# Sheet1.net
KiCad netlist of a schematic drawn in Altium Designer
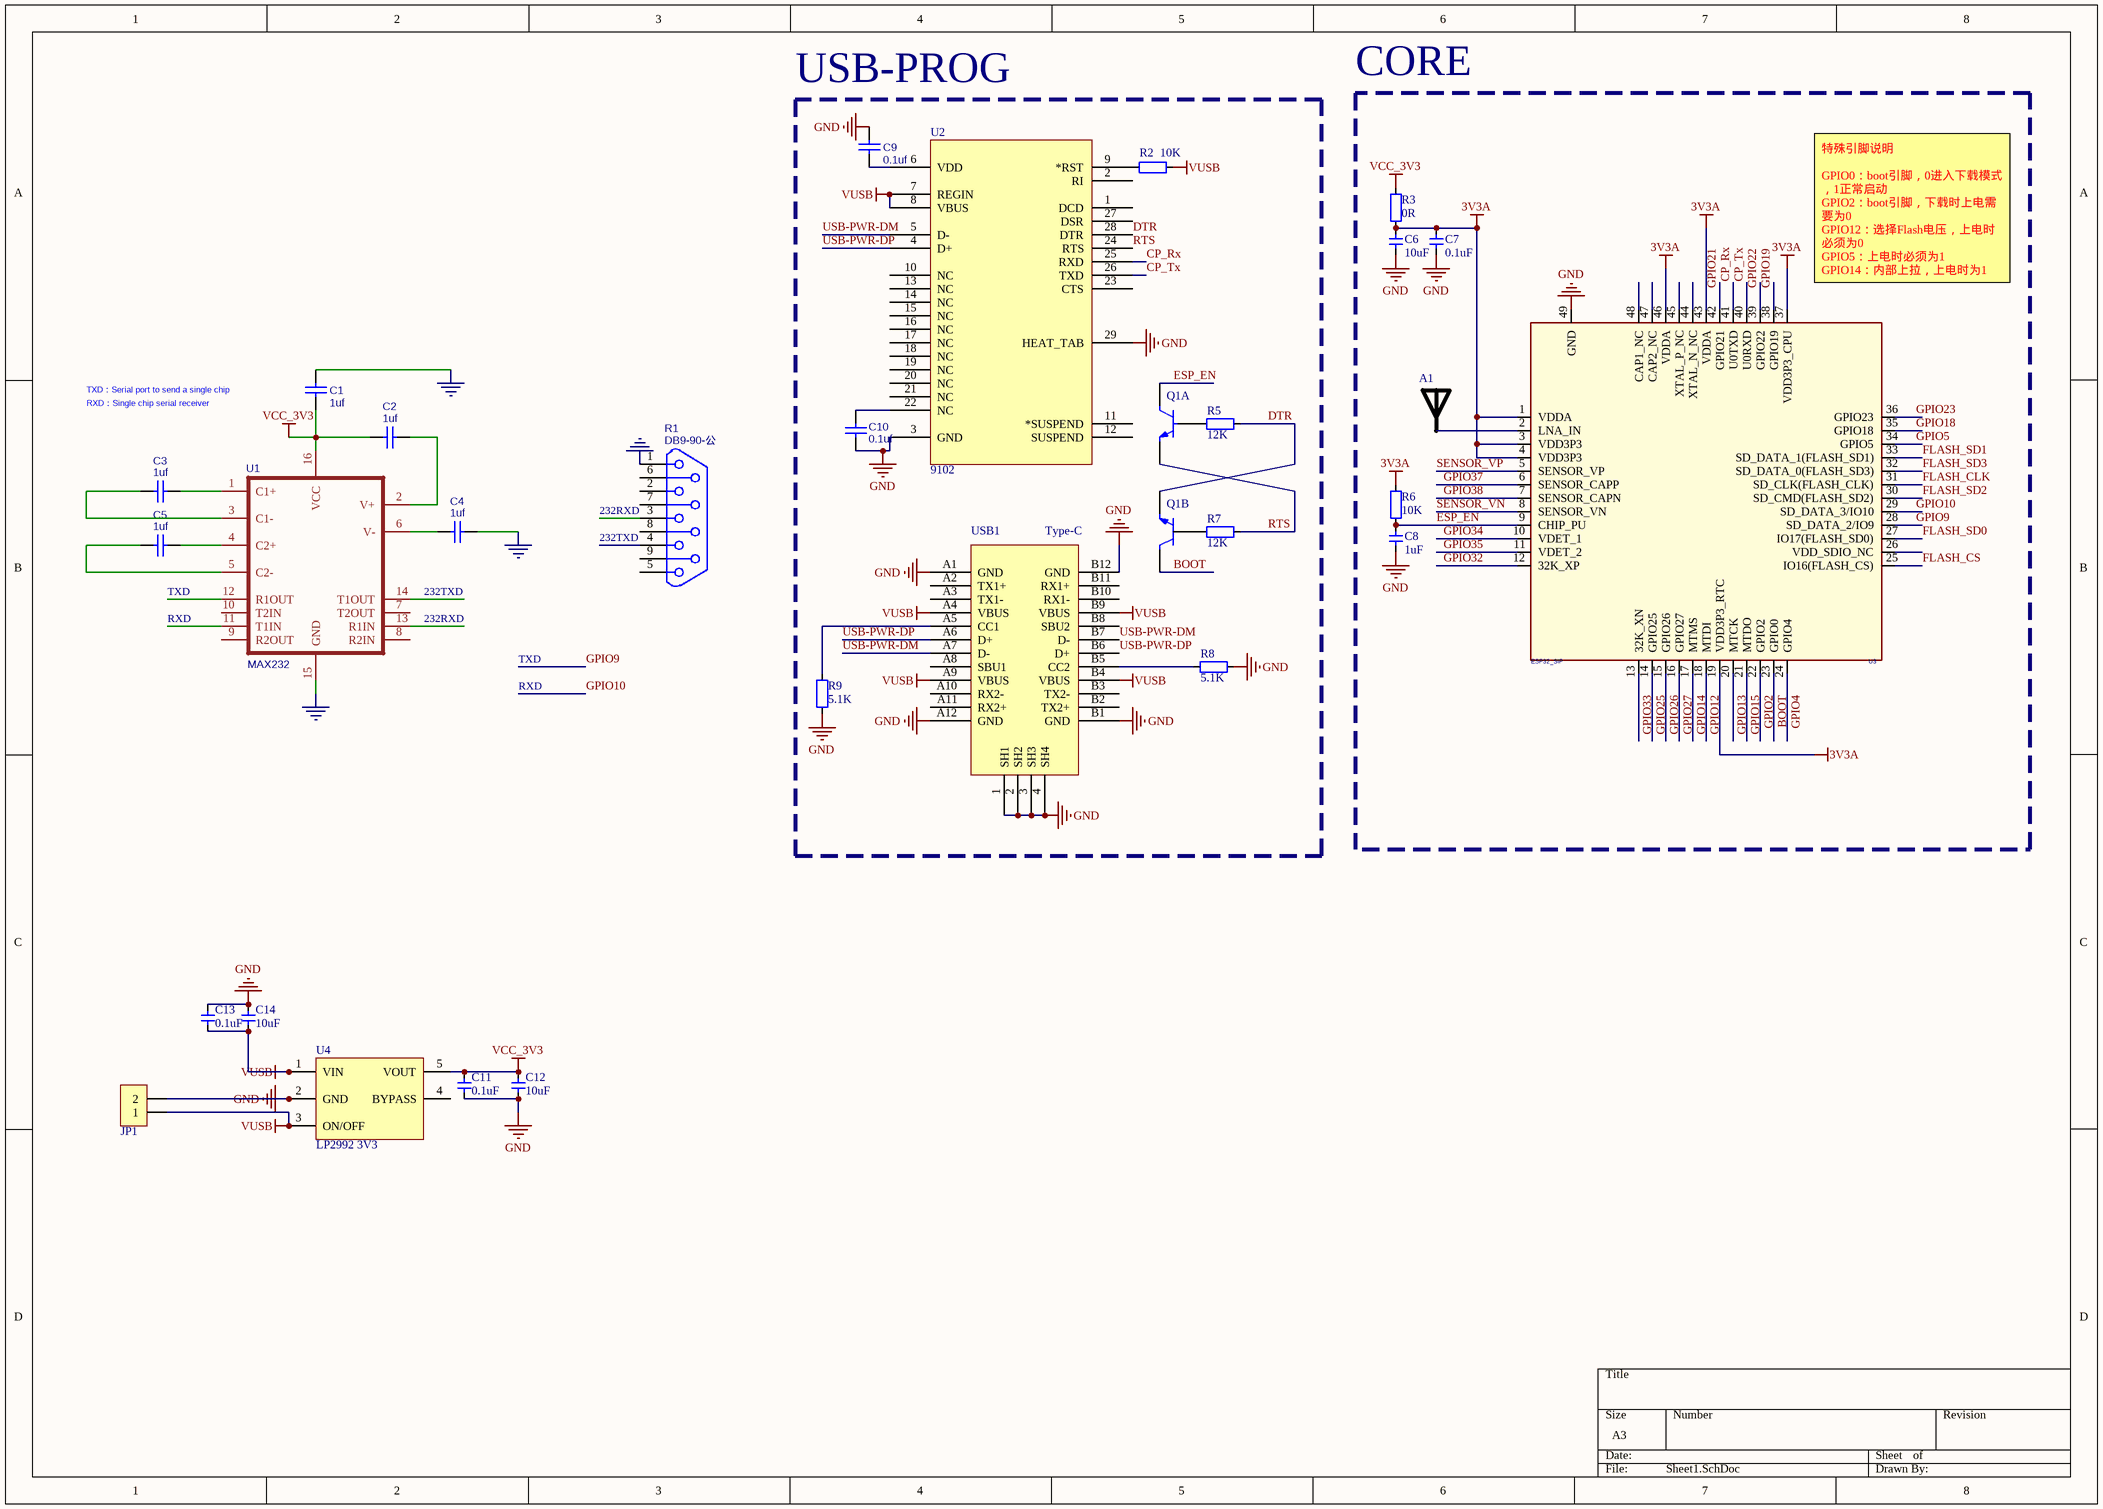
[diagram p0: Sheet1.SchDoc]

(export (version "E")
  (design (tool "Eeschema 10.0.6"))
  (components
    (comp (ref "A1")
      (value "RAINSUN")
      (footprint "ANT-Rainsun-AN5120")
      (libsource (lib "MyPcbLib") (part "ANT-Rainsun-AP5120"))
    )
    (comp (ref "C1")
      (value "1uf")
      (footprint "C0402_M")
      (fields (field (name "BOM_MANUFACTURER PART") "?"))
      (libsource (lib "altium-import") (part "root_2_1uf_"))
    )
    (comp (ref "C2")
      (value "1uf")
      (footprint "C0402_M")
      (fields (field (name "BOM_MANUFACTURER PART") "?"))
      (libsource (lib "altium-import") (part "root_1_1uf_"))
    )
    (comp (ref "C3")
      (value "1uf")
      (footprint "C0402_M")
      (fields (field (name "BOM_MANUFACTURER PART") "?"))
      (libsource (lib "altium-import") (part "root_1_1uf_"))
    )
    (comp (ref "C4")
      (value "1uf")
      (footprint "C0402_M")
      (fields (field (name "BOM_MANUFACTURER PART") "?"))
      (libsource (lib "altium-import") (part "root_1_1uf_"))
    )
    (comp (ref "C5")
      (value "1uf")
      (footprint "C0402_M")
      (fields (field (name "BOM_MANUFACTURER PART") "?"))
      (libsource (lib "altium-import") (part "root_1_1uf_"))
    )
    (comp (ref "C6")
      (value "10uF")
      (footprint "CAP_0402")
      (description "Capacitor")
      (libsource (lib "MyPcbLib") (part "电容-0402"))
    )
    (comp (ref "C7")
      (value "0.1uF")
      (footprint "CAP_0402")
      (description "Capacitor")
      (libsource (lib "MyPcbLib") (part "电容-0402"))
    )
    (comp (ref "C8")
      (value "1uF")
      (footprint "CAP_0402")
      (description "Capacitor")
      (libsource (lib "MyPcbLib") (part "电容-0402"))
    )
    (comp (ref "C9")
      (value "0.1uf")
      (footprint "C0402_M")
      (fields (field (name "BOM_MANUFACTURER PART") "?"))
      (libsource (lib "altium-import") (part "root_2_1uf_"))
    )
    (comp (ref "C10")
      (value "0.1uf")
      (footprint "C0402_M")
      (fields (field (name "BOM_MANUFACTURER PART") "?"))
      (libsource (lib "altium-import") (part "root_0_1uf_"))
    )
    (comp (ref "C11")
      (value "0.1uF")
      (footprint "CAP_0402")
      (description "Capacitor")
      (libsource (lib "MyPcbLib") (part "电容-0402"))
    )
    (comp (ref "C12")
      (value "10uF")
      (footprint "CAP_0402")
      (description "Capacitor")
      (libsource (lib "MyPcbLib") (part "电容-0402"))
    )
    (comp (ref "C13")
      (value "0.1uF")
      (footprint "CAP_0402")
      (description "Capacitor")
      (libsource (lib "MyPcbLib") (part "电容-0402"))
    )
    (comp (ref "C14")
      (value "10uF")
      (footprint "CAP_0402")
      (description "Capacitor")
      (libsource (lib "MyPcbLib") (part "电容-0402"))
    )
    (comp (ref "JP1")
      (value "HDR-1X2")
      (footprint "XH2.54-LI-2P")
      (description "2P接插件")
      (libsource (lib "5.5 - 2.54mm连接器(KF2EDGK_XH2.54_2.54排针排母)") (part "Header 2"))
    )
    (comp (ref "Q1")
      (value "BC847BVC-7")
      (footprint "SOT563-6")
      (libsource (lib "MyPcbLib") (part "BC847BVC-7"))
    )
    (comp (ref "R1")
      (value "DB9-90-公")
      (footprint "DSUB-TH_FDB0901-M0DB300K6KF")
      (fields (field (name "BOM_MANUFACTURER PART") "?"))
      (libsource (lib "altium-import") (part "root_0_DB9-90-公_"))
    )
    (comp (ref "R2")
      (value "10K")
      (footprint "RES_0402")
      (description "Resistor")
      (libsource (lib "") (part "电阻-0402_1"))
    )
    (comp (ref "R3")
      (value "0R")
      (footprint "RES_0402")
      (description "Resistor")
      (libsource (lib "MyPcbLib") (part "电阻-0402"))
    )
    (comp (ref "R5")
      (value "12K")
      (footprint "RES_0402")
      (description "Resistor")
      (libsource (lib "") (part "电阻-0402_1"))
    )
    (comp (ref "R6")
      (value "10K")
      (footprint "RES_0402")
      (description "Resistor")
      (libsource (lib "MyPcbLib") (part "电阻-0402"))
    )
    (comp (ref "R7")
      (value "12K")
      (footprint "RES_0402")
      (description "Resistor")
      (libsource (lib "") (part "电阻-0402_1"))
    )
    (comp (ref "R8")
      (value "5.1K")
      (footprint "RES_0402")
      (description "Resistor")
      (libsource (lib "") (part "电阻-0402_1"))
    )
    (comp (ref "R9")
      (value "5.1K")
      (footprint "RES_0402")
      (description "Resistor")
      (libsource (lib "MyPcbLib") (part "电阻-0402"))
    )
    (comp (ref "U1")
      (value "MAX232")
      (footprint "SO16")
      (fields (field (name "BOM_MANUFACTURER PART") "?") (field (name "CONTRIBUTOR") "SparkFun"))
      (libsource (lib "altium-import") (part "root_0_MAX232_"))
    )
    (comp (ref "U2")
      (value "9102")
      (footprint "QFN-28")
      (description "USB转TTL")
      (fields (field (name "PART NUMBER") "CP2102"))
      (libsource (lib "mLib") (part "CP2102"))
    )
    (comp (ref "U3")
      (value "ESP32_SIP")
      (footprint "QFN-48_7X7")
      (libsource (lib "mLib") (part "ESP32-PICO"))
    )
    (comp (ref "U4")
      (value "LP2992 3V3")
      (footprint "SOT23-5")
      (description "LDO")
      (libsource (lib "mLib") (part "LP2992"))
    )
    (comp (ref "USB1")
      (value "Type-C")
      (footprint "Type-C-TOP")
      (libsource (lib "MyPcbLib") (part "USB-Type-C-TOP"))
    )
  )
  (nets
    (net (code "1") (name "/232RXD") (class "Default")
      (node (ref "R1") (pin "3") (pinfunction "3_3") (pintype "passive"))
      (node (ref "U1") (pin "13") (pinfunction "R1IN_13") (pintype "passive"))
    )
    (net (code "2") (name "/232TXD") (class "Default")
      (node (ref "R1") (pin "4") (pinfunction "4_4") (pintype "passive"))
      (node (ref "U1") (pin "14") (pinfunction "T1OUT_14") (pintype "passive"))
    )
    (net (code "3") (name "/BOOT") (class "Default")
      (node (ref "Q1") (pin "3") (pinfunction "C2_3") (pintype "passive"))
      (node (ref "U3") (pin "23") (pinfunction "GPIO0_23") (pintype "passive"))
    )
    (net (code "4") (name "/CP_Rx") (class "Default")
      (node (ref "U2") (pin "25") (pinfunction "RXD_25") (pintype "passive"))
      (node (ref "U3") (pin "41") (pinfunction "U0TXD_41") (pintype "power_in"))
    )
    (net (code "5") (name "/CP_Tx") (class "Default")
      (node (ref "U2") (pin "26") (pinfunction "TXD_26") (pintype "passive"))
      (node (ref "U3") (pin "40") (pinfunction "U0RXD_40") (pintype "power_in"))
    )
    (net (code "6") (name "/DTR") (class "Default")
      (node (ref "Q1") (pin "4") (pinfunction "E2_4") (pintype "passive"))
      (node (ref "R5") (pin "1") (pinfunction "1_1") (pintype "passive"))
      (node (ref "U2") (pin "28") (pinfunction "DTR_28") (pintype "passive"))
    )
    (net (code "7") (name "/ESP_EN") (class "Default")
      (node (ref "C8") (pin "1") (pinfunction "1_1") (pintype "passive"))
      (node (ref "Q1") (pin "6") (pinfunction "C1_6") (pintype "passive"))
      (node (ref "R6") (pin "2") (pinfunction "2_2") (pintype "passive"))
      (node (ref "U3") (pin "9") (pinfunction "CHIP_PU_9") (pintype "passive"))
    )
    (net (code "8") (name "/FLASH_CLK") (class "Default")
      (node (ref "U3") (pin "31") (pinfunction "SD_CLK(FLASH_CLK)_31") (pintype "passive"))
    )
    (net (code "9") (name "/FLASH_CS") (class "Default")
      (node (ref "U3") (pin "25") (pinfunction "IO16(FLASH_CS)_25") (pintype "passive"))
    )
    (net (code "10") (name "/FLASH_SD0") (class "Default")
      (node (ref "U3") (pin "27") (pinfunction "IO17(FLASH_SD0)_27") (pintype "passive"))
    )
    (net (code "11") (name "/FLASH_SD1") (class "Default")
      (node (ref "U3") (pin "33") (pinfunction "SD_DATA_1(FLASH_SD1)_33") (pintype "passive"))
    )
    (net (code "12") (name "/FLASH_SD2") (class "Default")
      (node (ref "U3") (pin "30") (pinfunction "SD_CMD(FLASH_SD2)_30") (pintype "passive"))
    )
    (net (code "13") (name "/FLASH_SD3") (class "Default")
      (node (ref "U3") (pin "32") (pinfunction "SD_DATA_0(FLASH_SD3)_32") (pintype "passive"))
    )
    (net (code "14") (name "/GPIO2") (class "Default")
      (node (ref "U3") (pin "22") (pinfunction "GPIO2_22") (pintype "passive"))
    )
    (net (code "15") (name "/GPIO4") (class "Default")
      (node (ref "U3") (pin "24") (pinfunction "GPIO4_24") (pintype "passive"))
    )
    (net (code "16") (name "/GPIO5") (class "Default")
      (node (ref "U3") (pin "34") (pinfunction "GPIO5_34") (pintype "passive"))
    )
    (net (code "17") (name "/GPIO9") (class "Default")
      (node (ref "U1") (pin "12") (pinfunction "R1OUT_12") (pintype "passive"))
      (node (ref "U3") (pin "28") (pinfunction "SD_DATA_2/IO9_28") (pintype "passive"))
    )
    (net (code "18") (name "/GPIO10") (class "Default")
      (node (ref "U1") (pin "11") (pinfunction "T1IN_11") (pintype "passive"))
      (node (ref "U3") (pin "29") (pinfunction "SD_DATA_3/IO10_29") (pintype "passive"))
    )
    (net (code "19") (name "/GPIO12") (class "Default")
      (node (ref "U3") (pin "18") (pinfunction "MTDI_18") (pintype "passive"))
    )
    (net (code "20") (name "/GPIO13") (class "Default")
      (node (ref "U3") (pin "20") (pinfunction "MTCK_20") (pintype "passive"))
    )
    (net (code "21") (name "/GPIO14") (class "Default")
      (node (ref "U3") (pin "17") (pinfunction "MTMS_17") (pintype "passive"))
    )
    (net (code "22") (name "/GPIO15") (class "Default")
      (node (ref "U3") (pin "21") (pinfunction "MTDO_21") (pintype "passive"))
    )
    (net (code "23") (name "/GPIO18") (class "Default")
      (node (ref "U3") (pin "35") (pinfunction "GPIO18_35") (pintype "passive"))
    )
    (net (code "24") (name "/GPIO19") (class "Default")
      (node (ref "U3") (pin "38") (pinfunction "GPIO19_38") (pintype "passive"))
    )
    (net (code "25") (name "/GPIO21") (class "Default")
      (node (ref "U3") (pin "42") (pinfunction "GPIO21_42") (pintype "passive"))
    )
    (net (code "26") (name "/GPIO22") (class "Default")
      (node (ref "U3") (pin "39") (pinfunction "GPIO22_39") (pintype "passive"))
    )
    (net (code "27") (name "/GPIO23") (class "Default")
      (node (ref "U3") (pin "36") (pinfunction "GPIO23_36") (pintype "passive"))
    )
    (net (code "28") (name "/GPIO25") (class "Default")
      (node (ref "U3") (pin "14") (pinfunction "GPIO25_14") (pintype "passive"))
    )
    (net (code "29") (name "/GPIO26") (class "Default")
      (node (ref "U3") (pin "15") (pinfunction "GPIO26_15") (pintype "passive"))
    )
    (net (code "30") (name "/GPIO27") (class "Default")
      (node (ref "U3") (pin "16") (pinfunction "GPIO27_16") (pintype "passive"))
    )
    (net (code "31") (name "/GPIO32") (class "Default")
      (node (ref "U3") (pin "12") (pinfunction "32K_XP_12") (pintype "passive"))
    )
    (net (code "32") (name "/GPIO33") (class "Default")
      (node (ref "U3") (pin "13") (pinfunction "32K_XN_13") (pintype "passive"))
    )
    (net (code "33") (name "/GPIO34") (class "Default")
      (node (ref "U3") (pin "10") (pinfunction "VDET_1_10") (pintype "passive"))
    )
    (net (code "34") (name "/GPIO35") (class "Default")
      (node (ref "U3") (pin "11") (pinfunction "VDET_2_11") (pintype "passive"))
    )
    (net (code "35") (name "/GPIO37") (class "Default")
      (node (ref "U3") (pin "6") (pinfunction "SENSOR_CAPP_6") (pintype "passive"))
    )
    (net (code "36") (name "/GPIO38") (class "Default")
      (node (ref "U3") (pin "7") (pinfunction "SENSOR_CAPN_7") (pintype "passive"))
    )
    (net (code "37") (name "/RTS") (class "Default")
      (node (ref "Q1") (pin "1") (pinfunction "E1_1") (pintype "passive"))
      (node (ref "R7") (pin "1") (pinfunction "1_1") (pintype "passive"))
      (node (ref "U2") (pin "24") (pinfunction "RTS_24") (pintype "passive"))
    )
    (net (code "38") (name "/SENSOR_VN") (class "Default")
      (node (ref "U3") (pin "8") (pinfunction "SENSOR_VN_8") (pintype "passive"))
    )
    (net (code "39") (name "/SENSOR_VP") (class "Default")
      (node (ref "U3") (pin "5") (pinfunction "SENSOR_VP_5") (pintype "passive"))
    )
    (net (code "40") (name "/USB-PWR-DM") (class "Default")
      (node (ref "U2") (pin "5") (pinfunction "D-_5") (pintype "passive"))
      (node (ref "USB1") (pin "A7") (pinfunction "D-_A7") (pintype "passive"))
      (node (ref "USB1") (pin "B7") (pinfunction "D-_B7") (pintype "passive"))
    )
    (net (code "41") (name "/USB-PWR-DP") (class "Default")
      (node (ref "U2") (pin "4") (pinfunction "D+_4") (pintype "passive"))
      (node (ref "USB1") (pin "A6") (pinfunction "D+_A6") (pintype "passive"))
      (node (ref "USB1") (pin "B6") (pinfunction "D+_B6") (pintype "passive"))
    )
    (net (code "42") (name "3V3A") (class "Default")
      (node (ref "C6") (pin "2") (pinfunction "2_2") (pintype "passive"))
      (node (ref "C7") (pin "2") (pinfunction "2_2") (pintype "passive"))
      (node (ref "R3") (pin "2") (pinfunction "2_2") (pintype "passive"))
      (node (ref "R6") (pin "1") (pinfunction "1_1") (pintype "passive"))
      (node (ref "U3") (pin "1") (pinfunction "VDDA_1") (pintype "power_in"))
      (node (ref "U3") (pin "19") (pinfunction "VDD3P3_RTC_19") (pintype "power_in"))
      (node (ref "U3") (pin "3") (pinfunction "VDD3P3_3") (pintype "power_in"))
      (node (ref "U3") (pin "37") (pinfunction "VDD3P3_CPU_37") (pintype "power_in"))
      (node (ref "U3") (pin "4") (pinfunction "VDD3P3_4") (pintype "power_in"))
      (node (ref "U3") (pin "43") (pinfunction "VDDA_43") (pintype "power_in"))
      (node (ref "U3") (pin "46") (pinfunction "VDDA_46") (pintype "power_in"))
    )
    (net (code "43") (name "GND") (class "Default")
      (node (ref "C1") (pin "1") (pinfunction "1_1") (pintype "passive"))
      (node (ref "C10") (pin "1") (pinfunction "1_1") (pintype "passive"))
      (node (ref "C11") (pin "1") (pinfunction "1_1") (pintype "passive"))
      (node (ref "C12") (pin "1") (pinfunction "1_1") (pintype "passive"))
      (node (ref "C13") (pin "2") (pinfunction "2_2") (pintype "passive"))
      (node (ref "C14") (pin "2") (pinfunction "2_2") (pintype "passive"))
      (node (ref "C4") (pin "1") (pinfunction "1_1") (pintype "passive"))
      (node (ref "C6") (pin "1") (pinfunction "1_1") (pintype "passive"))
      (node (ref "C7") (pin "1") (pinfunction "1_1") (pintype "passive"))
      (node (ref "C8") (pin "2") (pinfunction "2_2") (pintype "passive"))
      (node (ref "C9") (pin "1") (pinfunction "1_1") (pintype "passive"))
      (node (ref "JP1") (pin "2") (pinfunction "2_2") (pintype "passive"))
      (node (ref "R1") (pin "1") (pinfunction "1_1") (pintype "passive"))
      (node (ref "R8") (pin "1") (pinfunction "1_1") (pintype "passive"))
      (node (ref "R9") (pin "2") (pinfunction "2_2") (pintype "passive"))
      (node (ref "U1") (pin "15") (pinfunction "GND_15") (pintype "passive"))
      (node (ref "U2") (pin "29") (pinfunction "HEAT_TAB_29") (pintype "passive"))
      (node (ref "U2") (pin "3") (pinfunction "GND_3") (pintype "passive"))
      (node (ref "U3") (pin "49") (pinfunction "GND_49") (pintype "power_in"))
      (node (ref "U4") (pin "2") (pinfunction "GND_2") (pintype "passive"))
      (node (ref "USB1") (pin "1") (pinfunction "SH1_1") (pintype "passive"))
      (node (ref "USB1") (pin "2") (pinfunction "SH2_2") (pintype "passive"))
      (node (ref "USB1") (pin "3") (pinfunction "SH3_3") (pintype "passive"))
      (node (ref "USB1") (pin "4") (pinfunction "SH4_4") (pintype "passive"))
      (node (ref "USB1") (pin "A1") (pinfunction "GND_A1") (pintype "passive"))
      (node (ref "USB1") (pin "A12") (pinfunction "GND_A12") (pintype "passive"))
      (node (ref "USB1") (pin "B1") (pinfunction "GND_B1") (pintype "passive"))
      (node (ref "USB1") (pin "B12") (pinfunction "GND_B12") (pintype "passive"))
    )
    (net (code "44") (name "Net-(C10-Pad2)") (class "Default")
      (node (ref "C10") (pin "2") (pinfunction "2_2") (pintype "passive"))
      (node (ref "U2") (pin "22") (pinfunction "NC_22") (pintype "passive"))
    )
    (net (code "45") (name "Net-(Q1A-B1)") (class "Default")
      (node (ref "Q1") (pin "2") (pinfunction "B1_2") (pintype "passive"))
      (node (ref "R5") (pin "2") (pinfunction "2_2") (pintype "passive"))
    )
    (net (code "46") (name "Net-(Q1B-B2)") (class "Default")
      (node (ref "Q1") (pin "5") (pinfunction "B2_5") (pintype "passive"))
      (node (ref "R7") (pin "2") (pinfunction "2_2") (pintype "passive"))
    )
    (net (code "47") (name "Net-(U1-C1+)") (class "Default")
      (node (ref "C3") (pin "1") (pinfunction "1_1") (pintype "passive"))
      (node (ref "U1") (pin "1") (pinfunction "C1+_1") (pintype "passive"))
    )
    (net (code "48") (name "Net-(U1-C1-)") (class "Default")
      (node (ref "C3") (pin "2") (pinfunction "2_2") (pintype "passive"))
      (node (ref "U1") (pin "3") (pinfunction "C1-_3") (pintype "passive"))
    )
    (net (code "49") (name "Net-(U1-C2+)") (class "Default")
      (node (ref "C5") (pin "1") (pinfunction "1_1") (pintype "passive"))
      (node (ref "U1") (pin "4") (pinfunction "C2+_4") (pintype "passive"))
    )
    (net (code "50") (name "Net-(U1-C2-)") (class "Default")
      (node (ref "C5") (pin "2") (pinfunction "2_2") (pintype "passive"))
      (node (ref "U1") (pin "5") (pinfunction "C2-_5") (pintype "passive"))
    )
    (net (code "51") (name "Net-(U1-V+)") (class "Default")
      (node (ref "C2") (pin "1") (pinfunction "1_1") (pintype "passive"))
      (node (ref "U1") (pin "2") (pinfunction "V+_2") (pintype "passive"))
    )
    (net (code "52") (name "Net-(U1-V-)") (class "Default")
      (node (ref "C4") (pin "2") (pinfunction "2_2") (pintype "passive"))
      (node (ref "U1") (pin "6") (pinfunction "V-_6") (pintype "passive"))
    )
    (net (code "53") (name "Net-(U2-*RST)") (class "Default")
      (node (ref "R2") (pin "2") (pinfunction "2_2") (pintype "passive"))
      (node (ref "U2") (pin "9") (pinfunction "*RST_9") (pintype "passive"))
    )
    (net (code "54") (name "Net-(U2-VDD)") (class "Default")
      (node (ref "C9") (pin "2") (pinfunction "2_2") (pintype "passive"))
      (node (ref "U2") (pin "6") (pinfunction "VDD_6") (pintype "passive"))
    )
    (net (code "55") (name "Net-(U3-LNA_IN)") (class "Default")
      (node (ref "A1") (pin "1") (pinfunction "1_1") (pintype "passive"))
      (node (ref "U3") (pin "2") (pinfunction "LNA_IN_2") (pintype "passive"))
    )
    (net (code "56") (name "Net-(USB1-CC1)") (class "Default")
      (node (ref "R9") (pin "1") (pinfunction "1_1") (pintype "passive"))
      (node (ref "USB1") (pin "A5") (pinfunction "CC1_A5") (pintype "passive"))
    )
    (net (code "57") (name "Net-(USB1-CC2)") (class "Default")
      (node (ref "R8") (pin "2") (pinfunction "2_2") (pintype "passive"))
      (node (ref "USB1") (pin "B5") (pinfunction "CC2_B5") (pintype "passive"))
    )
    (net (code "58") (name "VCC_3V3") (class "Default")
      (node (ref "C1") (pin "2") (pinfunction "2_2") (pintype "passive"))
      (node (ref "C11") (pin "2") (pinfunction "2_2") (pintype "passive"))
      (node (ref "C12") (pin "2") (pinfunction "2_2") (pintype "passive"))
      (node (ref "C2") (pin "2") (pinfunction "2_2") (pintype "passive"))
      (node (ref "R3") (pin "1") (pinfunction "1_1") (pintype "passive"))
      (node (ref "U1") (pin "16") (pinfunction "VCC_16") (pintype "passive"))
      (node (ref "U4") (pin "5") (pinfunction "VOUT_5") (pintype "passive"))
    )
    (net (code "59") (name "VUSB") (class "Default")
      (node (ref "C13") (pin "1") (pinfunction "1_1") (pintype "passive"))
      (node (ref "C14") (pin "1") (pinfunction "1_1") (pintype "passive"))
      (node (ref "JP1") (pin "1") (pinfunction "1_1") (pintype "passive"))
      (node (ref "R2") (pin "1") (pinfunction "1_1") (pintype "passive"))
      (node (ref "U2") (pin "7") (pinfunction "REGIN_7") (pintype "passive"))
      (node (ref "U2") (pin "8") (pinfunction "VBUS_8") (pintype "passive"))
      (node (ref "U4") (pin "1") (pinfunction "VIN_1") (pintype "passive"))
      (node (ref "U4") (pin "3") (pinfunction "ON/OFF_3") (pintype "passive"))
      (node (ref "USB1") (pin "A4") (pinfunction "VBUS_A4") (pintype "passive"))
      (node (ref "USB1") (pin "A9") (pinfunction "VBUS_A9") (pintype "passive"))
      (node (ref "USB1") (pin "B4") (pinfunction "VBUS_B4") (pintype "passive"))
      (node (ref "USB1") (pin "B9") (pinfunction "VBUS_B9") (pintype "passive"))
    )
    (net (code "60") (name "unconnected-(R1-Pad2)") (class "Default")
      (node (ref "R1") (pin "2") (pinfunction "2_2") (pintype "passive"))
    )
    (net (code "61") (name "unconnected-(R1-Pad5)") (class "Default")
      (node (ref "R1") (pin "5") (pinfunction "5_5") (pintype "passive"))
    )
    (net (code "62") (name "unconnected-(R1-Pad6)") (class "Default")
      (node (ref "R1") (pin "6") (pinfunction "6_6") (pintype "passive"))
    )
    (net (code "63") (name "unconnected-(R1-Pad7)") (class "Default")
      (node (ref "R1") (pin "7") (pinfunction "7_7") (pintype "passive"))
    )
    (net (code "64") (name "unconnected-(R1-Pad8)") (class "Default")
      (node (ref "R1") (pin "8") (pinfunction "8_8") (pintype "passive"))
    )
    (net (code "65") (name "unconnected-(R1-Pad9)") (class "Default")
      (node (ref "R1") (pin "9") (pinfunction "9_9") (pintype "passive"))
    )
    (net (code "66") (name "unconnected-(U1-R2IN-Pad8)") (class "Default")
      (node (ref "U1") (pin "8") (pinfunction "R2IN_8") (pintype "passive"))
    )
    (net (code "67") (name "unconnected-(U1-R2OUT-Pad9)") (class "Default")
      (node (ref "U1") (pin "9") (pinfunction "R2OUT_9") (pintype "passive"))
    )
    (net (code "68") (name "unconnected-(U1-T2IN-Pad10)") (class "Default")
      (node (ref "U1") (pin "10") (pinfunction "T2IN_10") (pintype "passive"))
    )
    (net (code "69") (name "unconnected-(U1-T2OUT-Pad7)") (class "Default")
      (node (ref "U1") (pin "7") (pinfunction "T2OUT_7") (pintype "passive"))
    )
    (net (code "70") (name "unconnected-(U2-*SUSPEND-Pad11)") (class "Default")
      (node (ref "U2") (pin "11") (pinfunction "*SUSPEND_11") (pintype "passive"))
    )
    (net (code "71") (name "unconnected-(U2-CTS-Pad23)") (class "Default")
      (node (ref "U2") (pin "23") (pinfunction "CTS_23") (pintype "passive"))
    )
    (net (code "72") (name "unconnected-(U2-DCD-Pad1)") (class "Default")
      (node (ref "U2") (pin "1") (pinfunction "DCD_1") (pintype "passive"))
    )
    (net (code "73") (name "unconnected-(U2-DSR-Pad27)") (class "Default")
      (node (ref "U2") (pin "27") (pinfunction "DSR_27") (pintype "passive"))
    )
    (net (code "74") (name "unconnected-(U2-NC-Pad10)") (class "Default")
      (node (ref "U2") (pin "10") (pinfunction "NC_10") (pintype "passive"))
    )
    (net (code "75") (name "unconnected-(U2-NC-Pad13)") (class "Default")
      (node (ref "U2") (pin "13") (pinfunction "NC_13") (pintype "passive"))
    )
    (net (code "76") (name "unconnected-(U2-NC-Pad14)") (class "Default")
      (node (ref "U2") (pin "14") (pinfunction "NC_14") (pintype "passive"))
    )
    (net (code "77") (name "unconnected-(U2-NC-Pad15)") (class "Default")
      (node (ref "U2") (pin "15") (pinfunction "NC_15") (pintype "passive"))
    )
    (net (code "78") (name "unconnected-(U2-NC-Pad16)") (class "Default")
      (node (ref "U2") (pin "16") (pinfunction "NC_16") (pintype "passive"))
    )
    (net (code "79") (name "unconnected-(U2-NC-Pad17)") (class "Default")
      (node (ref "U2") (pin "17") (pinfunction "NC_17") (pintype "passive"))
    )
    (net (code "80") (name "unconnected-(U2-NC-Pad18)") (class "Default")
      (node (ref "U2") (pin "18") (pinfunction "NC_18") (pintype "passive"))
    )
    (net (code "81") (name "unconnected-(U2-NC-Pad19)") (class "Default")
      (node (ref "U2") (pin "19") (pinfunction "NC_19") (pintype "passive"))
    )
    (net (code "82") (name "unconnected-(U2-NC-Pad20)") (class "Default")
      (node (ref "U2") (pin "20") (pinfunction "NC_20") (pintype "passive"))
    )
    (net (code "83") (name "unconnected-(U2-NC-Pad21)") (class "Default")
      (node (ref "U2") (pin "21") (pinfunction "NC_21") (pintype "passive"))
    )
    (net (code "84") (name "unconnected-(U2-RI-Pad2)") (class "Default")
      (node (ref "U2") (pin "2") (pinfunction "RI_2") (pintype "passive"))
    )
    (net (code "85") (name "unconnected-(U2-SUSPEND-Pad12)") (class "Default")
      (node (ref "U2") (pin "12") (pinfunction "SUSPEND_12") (pintype "passive"))
    )
    (net (code "86") (name "unconnected-(U3-CAP1_NC-Pad48)") (class "Default")
      (node (ref "U3") (pin "48") (pinfunction "CAP1_NC_48") (pintype "passive"))
    )
    (net (code "87") (name "unconnected-(U3-CAP2_NC-Pad47)") (class "Default")
      (node (ref "U3") (pin "47") (pinfunction "CAP2_NC_47") (pintype "passive"))
    )
    (net (code "88") (name "unconnected-(U3-VDD_SDIO_NC-Pad26)") (class "Default")
      (node (ref "U3") (pin "26") (pinfunction "VDD_SDIO_NC_26") (pintype "passive"))
    )
    (net (code "89") (name "unconnected-(U3-XTAL_N_NC-Pad44)") (class "Default")
      (node (ref "U3") (pin "44") (pinfunction "XTAL_N_NC_44") (pintype "passive"))
    )
    (net (code "90") (name "unconnected-(U3-XTAL_P_NC-Pad45)") (class "Default")
      (node (ref "U3") (pin "45") (pinfunction "XTAL_P_NC_45") (pintype "passive"))
    )
    (net (code "91") (name "unconnected-(U4-BYPASS-Pad4)") (class "Default")
      (node (ref "U4") (pin "4") (pinfunction "BYPASS_4") (pintype "passive"))
    )
    (net (code "92") (name "unconnected-(USB1-RX1+-PadB11)") (class "Default")
      (node (ref "USB1") (pin "B11") (pinfunction "RX1+_B11") (pintype "passive"))
    )
    (net (code "93") (name "unconnected-(USB1-RX1--PadB10)") (class "Default")
      (node (ref "USB1") (pin "B10") (pinfunction "RX1-_B10") (pintype "passive"))
    )
    (net (code "94") (name "unconnected-(USB1-RX2+-PadA11)") (class "Default")
      (node (ref "USB1") (pin "A11") (pinfunction "RX2+_A11") (pintype "passive"))
    )
    (net (code "95") (name "unconnected-(USB1-RX2--PadA10)") (class "Default")
      (node (ref "USB1") (pin "A10") (pinfunction "RX2-_A10") (pintype "passive"))
    )
    (net (code "96") (name "unconnected-(USB1-SBU1-PadA8)") (class "Default")
      (node (ref "USB1") (pin "A8") (pinfunction "SBU1_A8") (pintype "passive"))
    )
    (net (code "97") (name "unconnected-(USB1-SBU2-PadB8)") (class "Default")
      (node (ref "USB1") (pin "B8") (pinfunction "SBU2_B8") (pintype "passive"))
    )
    (net (code "98") (name "unconnected-(USB1-TX1+-PadA2)") (class "Default")
      (node (ref "USB1") (pin "A2") (pinfunction "TX1+_A2") (pintype "passive"))
    )
    (net (code "99") (name "unconnected-(USB1-TX1--PadA3)") (class "Default")
      (node (ref "USB1") (pin "A3") (pinfunction "TX1-_A3") (pintype "passive"))
    )
    (net (code "100") (name "unconnected-(USB1-TX2+-PadB2)") (class "Default")
      (node (ref "USB1") (pin "B2") (pinfunction "TX2+_B2") (pintype "passive"))
    )
    (net (code "101") (name "unconnected-(USB1-TX2--PadB3)") (class "Default")
      (node (ref "USB1") (pin "B3") (pinfunction "TX2-_B3") (pintype "passive"))
    )
  )
)
